# design.net
KiCad netlist of a schematic drawn in Altium Designer
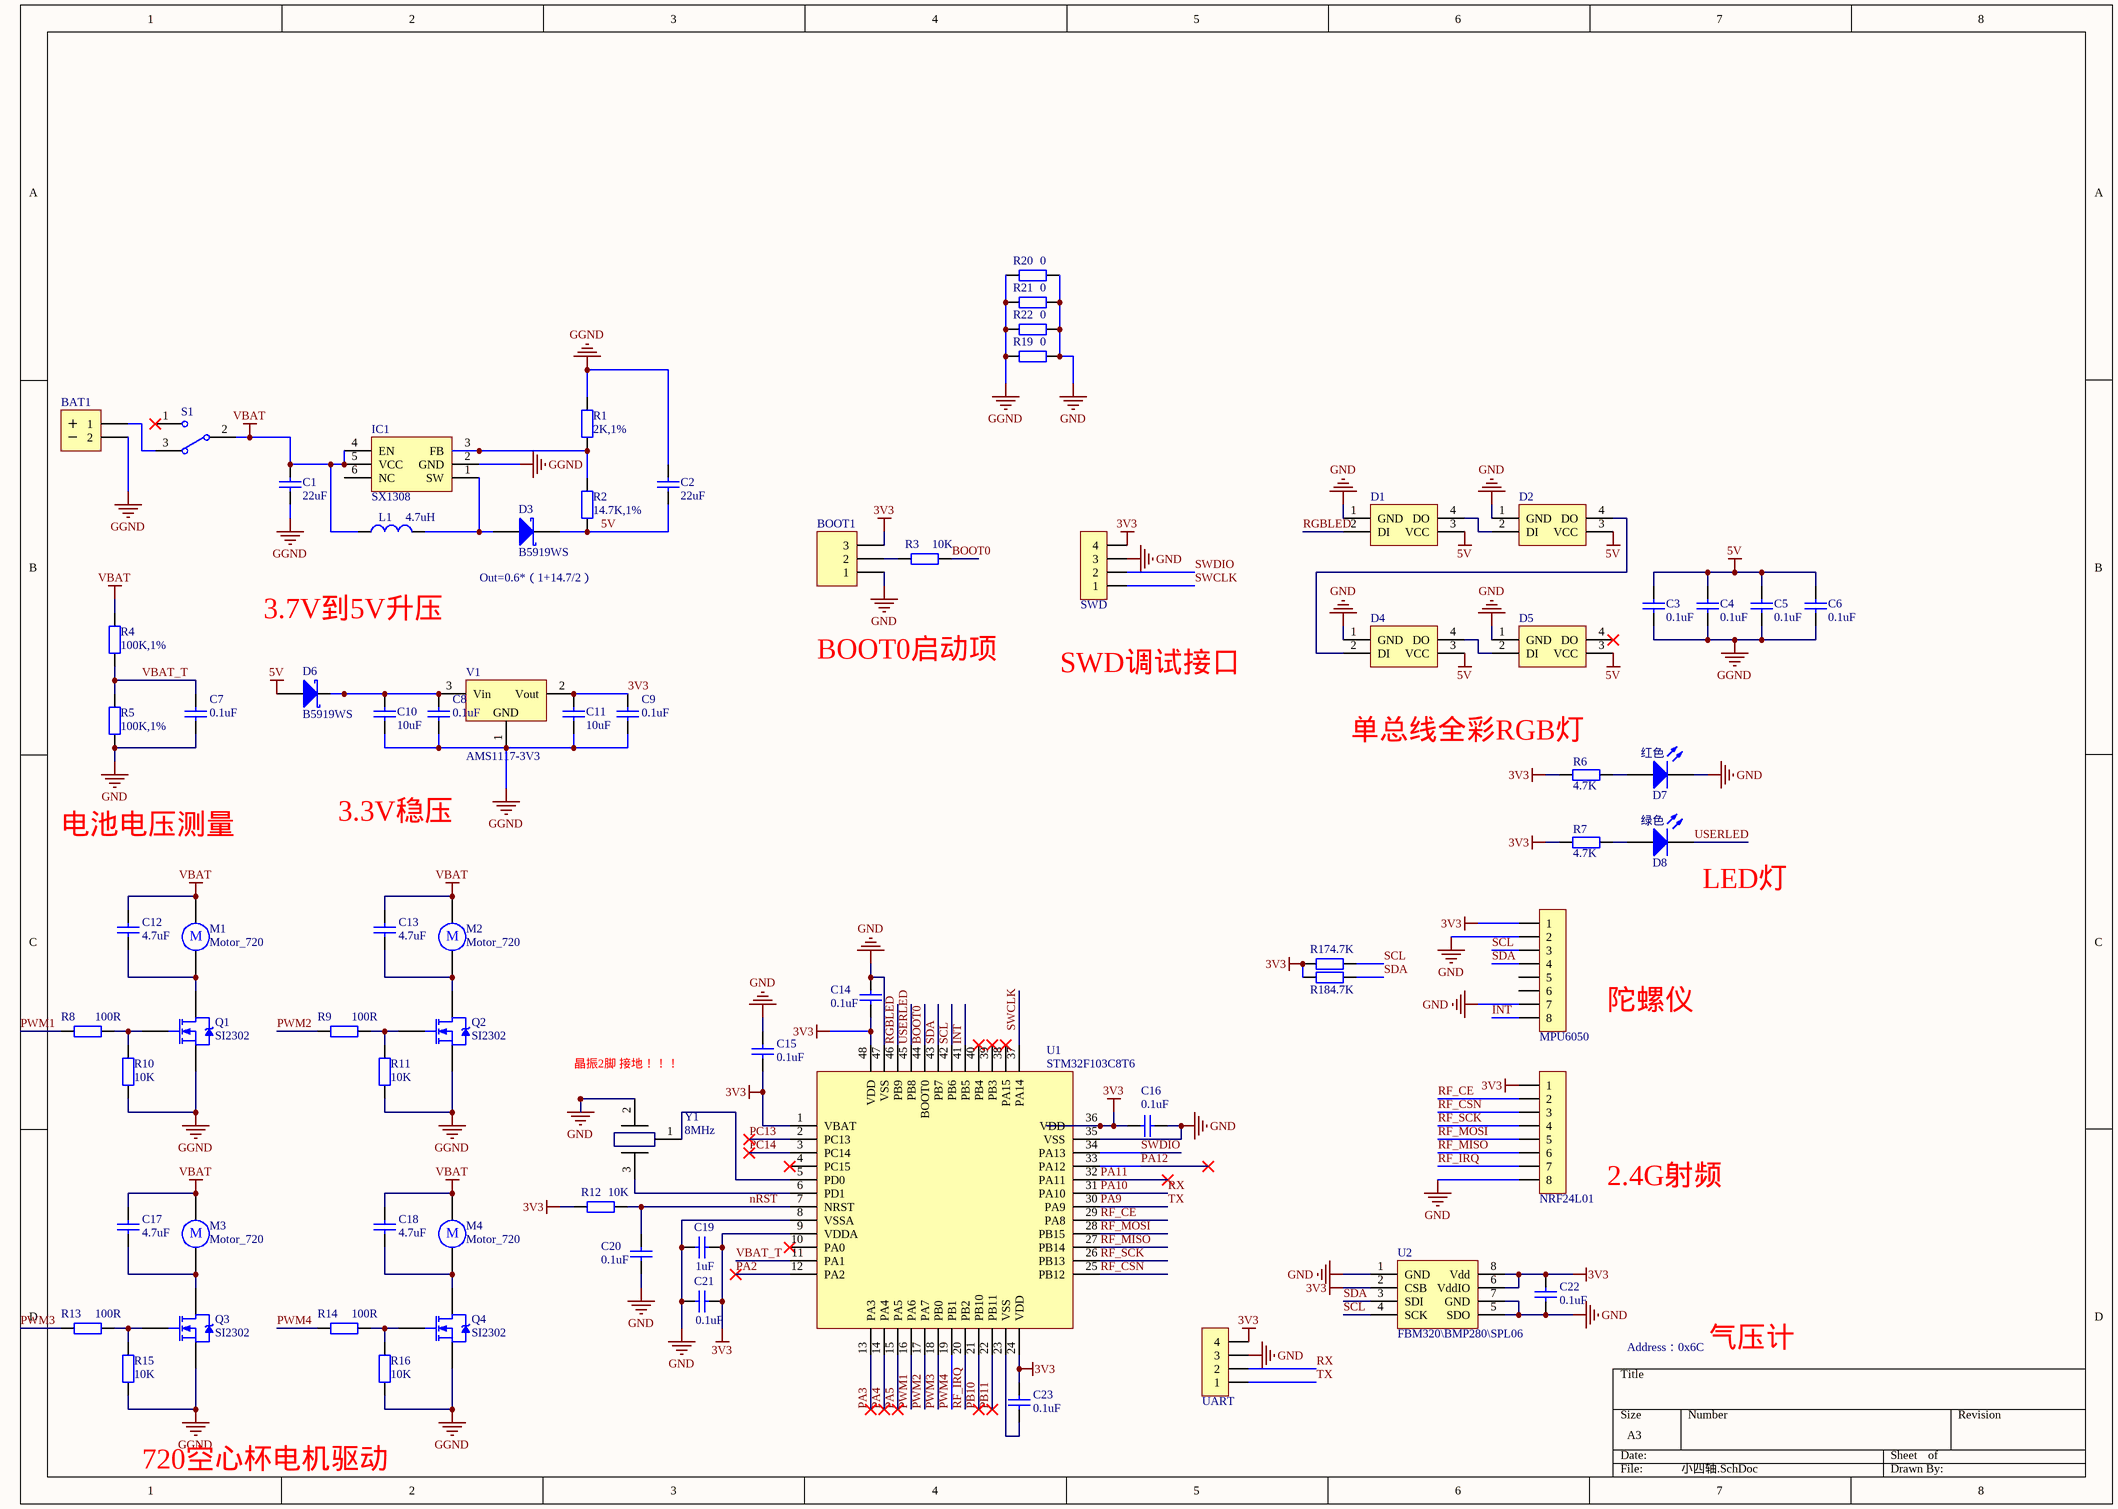
[diagram p0: 小四轴.SchDoc]

(export (version "E")
  (design (tool "Eeschema 10.0.6"))
  (components
    (comp (ref "BAT1")
      (value "BAT")
      (footprint "HDR2.54-LI-2P")
      (description "Header, 2-Pin")
      (fields (field (name "PUBLISHER") "mazhongwei"))
      (libsource (lib "RoboFly") (part "BAT"))
    )
    (comp (ref "BOOT1")
      (value "BOOT")
      (footprint "HDR2.54-LI-3P")
      (description "Header, 3-Pin")
      (fields (field (name "PUBLISHER") "Altium Limited"))
      (libsource (lib "RoboFly") (part "Header 3"))
    )
    (comp (ref "C1")
      (value "22uF")
      (footprint "C 0603_M")
      (fields (field (name "Comment") "C_0603") (field (name "PUBLISHER") "Altium Limited"))
      (libsource (lib "RoboFly") (part "C_0603"))
    )
    (comp (ref "C2")
      (value "22uF")
      (footprint "C 0603_M")
      (fields (field (name "Comment") "C_0603") (field (name "PUBLISHER") "Altium Limited"))
      (libsource (lib "RoboFly") (part "C_0603"))
    )
    (comp (ref "C3")
      (value "0.1uF")
      (footprint "C 0603_M")
      (fields (field (name "Comment") "C_0603") (field (name "PUBLISHER") "Altium Limited"))
      (libsource (lib "RoboFly") (part "C_0603"))
    )
    (comp (ref "C4")
      (value "0.1uF")
      (footprint "C 0603_M")
      (fields (field (name "Comment") "C_0603") (field (name "PUBLISHER") "Altium Limited"))
      (libsource (lib "RoboFly") (part "C_0603"))
    )
    (comp (ref "C5")
      (value "0.1uF")
      (footprint "C 0603_M")
      (fields (field (name "Comment") "C_0603") (field (name "PUBLISHER") "Altium Limited"))
      (libsource (lib "RoboFly") (part "C_0603"))
    )
    (comp (ref "C6")
      (value "0.1uF")
      (footprint "C 0603_M")
      (fields (field (name "Comment") "C_0603") (field (name "PUBLISHER") "Altium Limited"))
      (libsource (lib "RoboFly") (part "C_0603"))
    )
    (comp (ref "C7")
      (value "0.1uF")
      (footprint "C 0603_M")
      (fields (field (name "Comment") "C_0603") (field (name "PUBLISHER") "Altium Limited"))
      (libsource (lib "RoboFly") (part "C_0603"))
    )
    (comp (ref "C8")
      (value "0.1uF")
      (footprint "C 0603_M")
      (fields (field (name "Comment") "C_0603") (field (name "PUBLISHER") "Altium Limited"))
      (libsource (lib "RoboFly") (part "C_0603"))
    )
    (comp (ref "C9")
      (value "0.1uF")
      (footprint "C 0603_M")
      (fields (field (name "Comment") "C_0603") (field (name "PUBLISHER") "Altium Limited"))
      (libsource (lib "RoboFly") (part "C_0603"))
    )
    (comp (ref "C10")
      (value "10uF")
      (footprint "C 0603_M")
      (fields (field (name "Comment") "C_0603") (field (name "PUBLISHER") "Altium Limited"))
      (libsource (lib "RoboFly") (part "C_0603"))
    )
    (comp (ref "C11")
      (value "10uF")
      (footprint "C 0603_M")
      (fields (field (name "Comment") "C_0603") (field (name "PUBLISHER") "Altium Limited"))
      (libsource (lib "RoboFly") (part "C_0603"))
    )
    (comp (ref "C12")
      (value "4.7uF")
      (footprint "C 0603_M")
      (fields (field (name "Comment") "C_0603") (field (name "PUBLISHER") "Altium Limited"))
      (libsource (lib "RoboFly") (part "C_0603"))
    )
    (comp (ref "C13")
      (value "4.7uF")
      (footprint "C 0603_M")
      (fields (field (name "Comment") "C_0603") (field (name "PUBLISHER") "Altium Limited"))
      (libsource (lib "RoboFly") (part "C_0603"))
    )
    (comp (ref "C14")
      (value "0.1uF")
      (footprint "C 0603_M")
      (fields (field (name "Comment") "C_0603") (field (name "PUBLISHER") "Altium Limited"))
      (libsource (lib "RoboFly") (part "C_0603"))
    )
    (comp (ref "C15")
      (value "0.1uF")
      (footprint "C 0603_M")
      (fields (field (name "Comment") "C_0603") (field (name "PUBLISHER") "Altium Limited"))
      (libsource (lib "RoboFly") (part "C_0603"))
    )
    (comp (ref "C16")
      (value "0.1uF")
      (footprint "C 0603_M")
      (fields (field (name "Comment") "C_0603") (field (name "PUBLISHER") "Altium Limited"))
      (libsource (lib "RoboFly") (part "C_0603"))
    )
    (comp (ref "C17")
      (value "4.7uF")
      (footprint "C 0603_M")
      (fields (field (name "Comment") "C_0603") (field (name "PUBLISHER") "Altium Limited"))
      (libsource (lib "RoboFly") (part "C_0603"))
    )
    (comp (ref "C18")
      (value "4.7uF")
      (footprint "C 0603_M")
      (fields (field (name "Comment") "C_0603") (field (name "PUBLISHER") "Altium Limited"))
      (libsource (lib "RoboFly") (part "C_0603"))
    )
    (comp (ref "C19")
      (value "1uF")
      (footprint "C 0603_M")
      (fields (field (name "Comment") "C_0603") (field (name "PUBLISHER") "Altium Limited"))
      (libsource (lib "RoboFly") (part "C_0603"))
    )
    (comp (ref "C20")
      (value "0.1uF")
      (footprint "C 0603_M")
      (fields (field (name "Comment") "C_0603") (field (name "PUBLISHER") "Altium Limited"))
      (libsource (lib "RoboFly") (part "C_0603"))
    )
    (comp (ref "C21")
      (value "0.1uF")
      (footprint "C 0603_M")
      (fields (field (name "Comment") "C_0603") (field (name "PUBLISHER") "Altium Limited"))
      (libsource (lib "RoboFly") (part "C_0603"))
    )
    (comp (ref "C22")
      (value "0.1uF")
      (footprint "C 0603_M")
      (fields (field (name "Comment") "C_0603") (field (name "PUBLISHER") "Altium Limited"))
      (libsource (lib "RoboFly") (part "C_0603"))
    )
    (comp (ref "C23")
      (value "0.1uF")
      (footprint "C 0603_M")
      (fields (field (name "Comment") "C_0603") (field (name "PUBLISHER") "Altium Limited"))
      (libsource (lib "RoboFly") (part "C_0603"))
    )
    (comp (ref "D1")
      (value "P923D")
      (footprint "RGB_LED_5050")
      (fields (field (name "PUBLISHER") "mazhongwei"))
      (libsource (lib "RoboFly") (part "P923D"))
    )
    (comp (ref "D2")
      (value "P923D")
      (footprint "RGB_LED_5050")
      (fields (field (name "PUBLISHER") "mazhongwei"))
      (libsource (lib "RoboFly") (part "P923D"))
    )
    (comp (ref "D3")
      (value "B5919WS")
      (footprint "SOD-323")
      (description "肖特基二极管")
      (libsource (lib "二极管") (part "1N5819"))
    )
    (comp (ref "D4")
      (value "P923D")
      (footprint "RGB_LED_5050")
      (fields (field (name "PUBLISHER") "mazhongwei"))
      (libsource (lib "RoboFly") (part "P923D"))
    )
    (comp (ref "D5")
      (value "P923D")
      (footprint "RGB_LED_5050")
      (fields (field (name "PUBLISHER") "mazhongwei"))
      (libsource (lib "RoboFly") (part "P923D"))
    )
    (comp (ref "D6")
      (value "B5919WS")
      (footprint "SOD-323")
      (description "肖特基二极管")
      (libsource (lib "二极管") (part "1N5819"))
    )
    (comp (ref "D7")
      (value "红色")
      (footprint "LED 0603B")
      (description "发光二极管")
      (fields (field (name "PUBLISHER") "Altium Limited"))
      (libsource (lib "RoboFly") (part "LED 0603"))
    )
    (comp (ref "D8")
      (value "绿色")
      (footprint "LED 0603B")
      (description "发光二极管")
      (fields (field (name "PUBLISHER") "Altium Limited"))
      (libsource (lib "RoboFly") (part "LED 0603"))
    )
    (comp (ref "IC1")
      (value "SX1308")
      (footprint "SOT23-6N")
      (description "可调升压芯片")
      (fields (field (name "版权归属") "封装库来自淘宝 ID：黄晶宝石"))
      (libsource (lib "电源类芯片") (part "SX1308"))
    )
    (comp (ref "L1")
      (value "4.7uH")
      (footprint "SWPA4012S")
      (description "电感")
      (fields (field (name "Comment") "Inductor") (field (name "PUBLISHER") "Altium Limited"))
      (libsource (lib "RoboFly") (part "Inductor"))
    )
    (comp (ref "M1")
      (value "Motor_720")
      (footprint "ZH1.5-LI-2p")
      (description "Motor, General Kind")
      (fields (field (name "PUBLISHER") "mazhongwei"))
      (libsource (lib "RoboFly") (part "Motor_720"))
    )
    (comp (ref "M2")
      (value "Motor_720")
      (footprint "ZH1.5-LI-2p")
      (description "Motor, General Kind")
      (fields (field (name "PUBLISHER") "mazhongwei"))
      (libsource (lib "RoboFly") (part "Motor_720"))
    )
    (comp (ref "M3")
      (value "Motor_720")
      (footprint "ZH1.5-LI-2p")
      (description "Motor, General Kind")
      (fields (field (name "PUBLISHER") "mazhongwei"))
      (libsource (lib "RoboFly") (part "Motor_720"))
    )
    (comp (ref "M4")
      (value "Motor_720")
      (footprint "ZH1.5-LI-2p")
      (description "Motor, General Kind")
      (fields (field (name "PUBLISHER") "mazhongwei"))
      (libsource (lib "RoboFly") (part "Motor_720"))
    )
    (comp (ref "MPU6050")
      (value "HDR-1X8")
      (footprint "HDR2.54-LI-8P")
      (description "8P接插件")
      (fields (field (name "版权归属") "封装库来自淘宝 ID：黄晶宝石"))
      (libsource (lib "接插件-2.54MM") (part "Header 8"))
    )
    (comp (ref "NRF24L01")
      (value "HDR-1X8")
      (footprint "HDR1.27-LI-8P")
      (description "8P接插件")
      (libsource (lib "接插件-1.27MM") (part "Header 8"))
    )
    (comp (ref "Q1")
      (value "SI2302")
      (footprint "SOT23-3M")
      (description "N-Channel Power MOSFET")
      (fields (field (name "PUBLISHER") "mazhongwei"))
      (libsource (lib "RoboFly") (part "SI2302"))
    )
    (comp (ref "Q2")
      (value "SI2302")
      (footprint "SOT23-3M")
      (description "N-Channel Power MOSFET")
      (fields (field (name "PUBLISHER") "mazhongwei"))
      (libsource (lib "RoboFly") (part "SI2302"))
    )
    (comp (ref "Q3")
      (value "SI2302")
      (footprint "SOT23-3M")
      (description "N-Channel Power MOSFET")
      (fields (field (name "PUBLISHER") "mazhongwei"))
      (libsource (lib "RoboFly") (part "SI2302"))
    )
    (comp (ref "Q4")
      (value "SI2302")
      (footprint "SOT23-3M")
      (description "N-Channel Power MOSFET")
      (fields (field (name "PUBLISHER") "mazhongwei"))
      (libsource (lib "RoboFly") (part "SI2302"))
    )
    (comp (ref "R1")
      (value "2K,1%")
      (footprint "R 0603_M")
      (fields (field (name "Comment") "R_0603") (field (name "PUBLISHER") "Altium Limited"))
      (libsource (lib "") (part "R_0603_1"))
    )
    (comp (ref "R2")
      (value "14.7K,1%")
      (footprint "R 0603_M")
      (fields (field (name "Comment") "R_0603") (field (name "PUBLISHER") "Altium Limited"))
      (libsource (lib "") (part "R_0603_1"))
    )
    (comp (ref "R3")
      (value "10K")
      (footprint "R 0603_M")
      (fields (field (name "Comment") "R_0603") (field (name "PUBLISHER") "Altium Limited"))
      (libsource (lib "RoboFly") (part "R_0603"))
    )
    (comp (ref "R4")
      (value "100K,1%")
      (footprint "R 0603_M")
      (fields (field (name "Comment") "R_0603") (field (name "PUBLISHER") "Altium Limited"))
      (libsource (lib "") (part "R_0603_1"))
    )
    (comp (ref "R5")
      (value "100K,1%")
      (footprint "R 0603_M")
      (fields (field (name "Comment") "R_0603") (field (name "PUBLISHER") "Altium Limited"))
      (libsource (lib "") (part "R_0603_1"))
    )
    (comp (ref "R6")
      (value "4.7K")
      (footprint "R 0603_M")
      (fields (field (name "Comment") "R_0603") (field (name "PUBLISHER") "Altium Limited"))
      (libsource (lib "RoboFly") (part "R_0603"))
    )
    (comp (ref "R7")
      (value "4.7K")
      (footprint "R 0603_M")
      (fields (field (name "Comment") "R_0603") (field (name "PUBLISHER") "Altium Limited"))
      (libsource (lib "RoboFly") (part "R_0603"))
    )
    (comp (ref "R8")
      (value "100R")
      (footprint "R 0603_M")
      (fields (field (name "Comment") "R_0603") (field (name "PUBLISHER") "Altium Limited"))
      (libsource (lib "RoboFly") (part "R_0603"))
    )
    (comp (ref "R9")
      (value "100R")
      (footprint "R 0603_M")
      (fields (field (name "Comment") "R_0603") (field (name "PUBLISHER") "Altium Limited"))
      (libsource (lib "RoboFly") (part "R_0603"))
    )
    (comp (ref "R10")
      (value "10K")
      (footprint "R 0603_M")
      (fields (field (name "Comment") "R_0603") (field (name "PUBLISHER") "Altium Limited"))
      (libsource (lib "") (part "R_0603_1"))
    )
    (comp (ref "R11")
      (value "10K")
      (footprint "R 0603_M")
      (fields (field (name "Comment") "R_0603") (field (name "PUBLISHER") "Altium Limited"))
      (libsource (lib "") (part "R_0603_1"))
    )
    (comp (ref "R12")
      (value "10K")
      (footprint "R 0603_M")
      (fields (field (name "Comment") "R_0603") (field (name "PUBLISHER") "Altium Limited"))
      (libsource (lib "") (part "R_0603_2"))
    )
    (comp (ref "R13")
      (value "100R")
      (footprint "R 0603_M")
      (fields (field (name "Comment") "R_0603") (field (name "PUBLISHER") "Altium Limited"))
      (libsource (lib "RoboFly") (part "R_0603"))
    )
    (comp (ref "R14")
      (value "100R")
      (footprint "R 0603_M")
      (fields (field (name "Comment") "R_0603") (field (name "PUBLISHER") "Altium Limited"))
      (libsource (lib "RoboFly") (part "R_0603"))
    )
    (comp (ref "R15")
      (value "10K")
      (footprint "R 0603_M")
      (fields (field (name "Comment") "R_0603") (field (name "PUBLISHER") "Altium Limited"))
      (libsource (lib "") (part "R_0603_1"))
    )
    (comp (ref "R16")
      (value "10K")
      (footprint "R 0603_M")
      (fields (field (name "Comment") "R_0603") (field (name "PUBLISHER") "Altium Limited"))
      (libsource (lib "") (part "R_0603_1"))
    )
    (comp (ref "R17")
      (value "4.7K")
      (footprint "R 0603_M")
      (fields (field (name "Comment") "R_0603") (field (name "PUBLISHER") "Altium Limited"))
      (libsource (lib "RoboFly") (part "R_0603"))
    )
    (comp (ref "R18")
      (value "4.7K")
      (footprint "R 0603_M")
      (fields (field (name "Comment") "R_0603") (field (name "PUBLISHER") "Altium Limited"))
      (libsource (lib "RoboFly") (part "R_0603"))
    )
    (comp (ref "R19")
      (value "0")
      (footprint "R 0603_M")
      (fields (field (name "Comment") "R_0603") (field (name "PUBLISHER") "Altium Limited"))
      (libsource (lib "RoboFly") (part "R_0603"))
    )
    (comp (ref "R20")
      (value "0")
      (footprint "R 0603_M")
      (fields (field (name "Comment") "R_0603") (field (name "PUBLISHER") "Altium Limited"))
      (libsource (lib "RoboFly") (part "R_0603"))
    )
    (comp (ref "R21")
      (value "0")
      (footprint "R 0603_M")
      (fields (field (name "Comment") "R_0603") (field (name "PUBLISHER") "Altium Limited"))
      (libsource (lib "RoboFly") (part "R_0603"))
    )
    (comp (ref "R22")
      (value "0")
      (footprint "R 0603_M")
      (fields (field (name "Comment") "R_0603") (field (name "PUBLISHER") "Altium Limited"))
      (libsource (lib "RoboFly") (part "R_0603"))
    )
    (comp (ref "S1")
      (value "SW-SPDT")
      (footprint "SW-TH_OS102011MS2QN1")
      (description "SPDT Subminiature Toggle Switch, Right Angle Mounting, Vertical Actuation")
      (fields (field (name "PUBLISHER") "mazhongwei"))
      (libsource (lib "RoboFly") (part "SW-SPDT"))
    )
    (comp (ref "SWD")
      (value "HDR-1X4")
      (footprint "HDR2.54-LI-4P")
      (description "4P接插件")
      (fields (field (name "版权归属") "封装库来自淘宝 ID：黄晶宝石"))
      (libsource (lib "接插件-2.54MM") (part "Header 4"))
    )
    (comp (ref "U1")
      (value "STM32F103C8T6")
      (footprint "LQFP48-7*7")
      (libsource (lib "RoboFly") (part "STM32F103C8T6"))
    )
    (comp (ref "U2")
      (value "FBM32~{0}BMP28~{0}SPL06")
      (footprint "SENSOR-TH_BMP280-BL")
      (description "气压计")
      (fields (field (name "PUBLISHER") "mazhongwei"))
      (libsource (lib "RoboFly") (part "FBM320"))
    )
    (comp (ref "UART")
      (value "HDR-1X4")
      (footprint "HDR2.54-LI-4P")
      (description "4P接插件")
      (fields (field (name "版权归属") "封装库来自淘宝 ID：黄晶宝石"))
      (libsource (lib "接插件-2.54MM") (part "Header 4"))
    )
    (comp (ref "V1")
      (value "AMS1117-3V3")
      (footprint "SOT223_L")
      (description "三端稳压芯片")
      (libsource (lib "电源类芯片") (part "AMS1117"))
    )
    (comp (ref "Y1")
      (value "8MHz")
      (footprint "OSC-SMD_3P-L3.2-W1.3-P1.20-L")
      (fields (field (name "Comment") "XTAL") (field (name "PUBLISHER") "mazhongwei"))
      (libsource (lib "RoboFly") (part "XTAL_2"))
    )
  )
  (nets
    (net (code "1") (name "/BOOT0") (class "Default")
      (node (ref "R3") (pin "2") (pinfunction "2_2") (pintype "passive"))
      (node (ref "U1") (pin "44") (pinfunction "BOOT0_44") (pintype "passive"))
    )
    (net (code "2") (name "/INT") (class "Default")
      (node (ref "MPU6050") (pin "8") (pinfunction "8_8") (pintype "passive"))
      (node (ref "U1") (pin "41") (pinfunction "PB5_41") (pintype "passive"))
    )
    (net (code "3") (name "/PA2") (class "Default")
      (node (ref "U1") (pin "12") (pinfunction "PA2_12") (pintype "passive+no_connect"))
    )
    (net (code "4") (name "/PA3") (class "Default")
      (node (ref "U1") (pin "13") (pinfunction "PA3_13") (pintype "passive+no_connect"))
    )
    (net (code "5") (name "/PA4") (class "Default")
      (node (ref "U1") (pin "14") (pinfunction "PA4_14") (pintype "passive+no_connect"))
    )
    (net (code "6") (name "/PA5") (class "Default")
      (node (ref "U1") (pin "15") (pinfunction "PA5_15") (pintype "passive+no_connect"))
    )
    (net (code "7") (name "/PA9") (class "Default")
      (node (ref "U1") (pin "30") (pinfunction "PA9_30") (pintype "passive"))
      (node (ref "UART") (pin "1") (pinfunction "1_1") (pintype "passive"))
    )
    (net (code "8") (name "/PA10") (class "Default")
      (node (ref "U1") (pin "31") (pinfunction "PA10_31") (pintype "passive"))
      (node (ref "UART") (pin "2") (pinfunction "2_2") (pintype "passive"))
    )
    (net (code "9") (name "/PA11") (class "Default")
      (node (ref "U1") (pin "32") (pinfunction "PA11_32") (pintype "passive+no_connect"))
    )
    (net (code "10") (name "/PA12") (class "Default")
      (node (ref "U1") (pin "33") (pinfunction "PA12_33") (pintype "passive+no_connect"))
    )
    (net (code "11") (name "/PB10") (class "Default")
      (node (ref "U1") (pin "21") (pinfunction "PB10_21") (pintype "passive+no_connect"))
    )
    (net (code "12") (name "/PB11") (class "Default")
      (node (ref "U1") (pin "22") (pinfunction "PB11_22") (pintype "passive+no_connect"))
    )
    (net (code "13") (name "/PC13") (class "Default")
      (node (ref "U1") (pin "2") (pinfunction "PC13_2") (pintype "passive+no_connect"))
    )
    (net (code "14") (name "/PC14") (class "Default")
      (node (ref "U1") (pin "3") (pinfunction "PC14_3") (pintype "passive+no_connect"))
    )
    (net (code "15") (name "/PWM1") (class "Default")
      (node (ref "R8") (pin "1") (pinfunction "1_1") (pintype "passive"))
      (node (ref "U1") (pin "16") (pinfunction "PA6_16") (pintype "passive"))
    )
    (net (code "16") (name "/PWM2") (class "Default")
      (node (ref "R9") (pin "1") (pinfunction "1_1") (pintype "passive"))
      (node (ref "U1") (pin "17") (pinfunction "PA7_17") (pintype "passive"))
    )
    (net (code "17") (name "/PWM3") (class "Default")
      (node (ref "R13") (pin "1") (pinfunction "1_1") (pintype "passive"))
      (node (ref "U1") (pin "18") (pinfunction "PB0_18") (pintype "passive"))
    )
    (net (code "18") (name "/PWM4") (class "Default")
      (node (ref "R14") (pin "1") (pinfunction "1_1") (pintype "passive"))
      (node (ref "U1") (pin "19") (pinfunction "PB1_19") (pintype "passive"))
    )
    (net (code "19") (name "/RF_CE") (class "Default")
      (node (ref "NRF24L01") (pin "2") (pinfunction "2_2") (pintype "passive"))
      (node (ref "U1") (pin "29") (pinfunction "PA8_29") (pintype "passive"))
    )
    (net (code "20") (name "/RF_CSN") (class "Default")
      (node (ref "NRF24L01") (pin "3") (pinfunction "3_3") (pintype "passive"))
      (node (ref "U1") (pin "25") (pinfunction "PB12_25") (pintype "passive"))
    )
    (net (code "21") (name "/RF_IRQ") (class "Default")
      (node (ref "NRF24L01") (pin "7") (pinfunction "7_7") (pintype "passive"))
      (node (ref "U1") (pin "20") (pinfunction "PB2_20") (pintype "passive"))
    )
    (net (code "22") (name "/RF_MISO") (class "Default")
      (node (ref "NRF24L01") (pin "6") (pinfunction "6_6") (pintype "passive"))
      (node (ref "U1") (pin "27") (pinfunction "PB14_27") (pintype "passive"))
    )
    (net (code "23") (name "/RF_MOSI") (class "Default")
      (node (ref "NRF24L01") (pin "5") (pinfunction "5_5") (pintype "passive"))
      (node (ref "U1") (pin "28") (pinfunction "PB15_28") (pintype "passive"))
    )
    (net (code "24") (name "/RF_SCK") (class "Default")
      (node (ref "NRF24L01") (pin "4") (pinfunction "4_4") (pintype "passive"))
      (node (ref "U1") (pin "26") (pinfunction "PB13_26") (pintype "passive"))
    )
    (net (code "25") (name "/RGBLED") (class "Default")
      (node (ref "D1") (pin "2") (pinfunction "DI_2") (pintype "passive"))
      (node (ref "U1") (pin "46") (pinfunction "PB9_46") (pintype "passive"))
    )
    (net (code "26") (name "/SCL") (class "Default")
      (node (ref "MPU6050") (pin "3") (pinfunction "3_3") (pintype "passive"))
      (node (ref "R17") (pin "2") (pinfunction "2_2") (pintype "passive"))
      (node (ref "U1") (pin "42") (pinfunction "PB6_42") (pintype "passive"))
      (node (ref "U2") (pin "4") (pinfunction "SCK_4") (pintype "passive"))
    )
    (net (code "27") (name "/SDA") (class "Default")
      (node (ref "MPU6050") (pin "4") (pinfunction "4_4") (pintype "passive"))
      (node (ref "R18") (pin "2") (pinfunction "2_2") (pintype "passive"))
      (node (ref "U1") (pin "43") (pinfunction "PB7_43") (pintype "passive"))
      (node (ref "U2") (pin "3") (pinfunction "SDI_3") (pintype "passive"))
    )
    (net (code "28") (name "/SWCLK") (class "Default")
      (node (ref "SWD") (pin "1") (pinfunction "1_1") (pintype "passive"))
      (node (ref "U1") (pin "37") (pinfunction "PA14_37") (pintype "passive"))
    )
    (net (code "29") (name "/SWDIO") (class "Default")
      (node (ref "SWD") (pin "2") (pinfunction "2_2") (pintype "passive"))
      (node (ref "U1") (pin "34") (pinfunction "PA13_34") (pintype "passive"))
    )
    (net (code "30") (name "/USERLED") (class "Default")
      (node (ref "D8") (pin "2") (pinfunction "2_2") (pintype "passive"))
      (node (ref "U1") (pin "45") (pinfunction "PB8_45") (pintype "passive"))
    )
    (net (code "31") (name "/VBAT_T") (class "Default")
      (node (ref "C7") (pin "2") (pinfunction "2_2") (pintype "passive"))
      (node (ref "R4") (pin "1") (pinfunction "1_1") (pintype "passive"))
      (node (ref "R5") (pin "2") (pinfunction "2_2") (pintype "passive"))
      (node (ref "U1") (pin "11") (pinfunction "PA1_11") (pintype "passive"))
    )
    (net (code "32") (name "/nRST") (class "Default")
      (node (ref "C20") (pin "2") (pinfunction "2_2") (pintype "passive"))
      (node (ref "R12") (pin "1") (pinfunction "1_1") (pintype "passive"))
      (node (ref "U1") (pin "7") (pinfunction "NRST_7") (pintype "passive"))
    )
    (net (code "33") (name "3V3") (class "Default")
      (node (ref "BOOT1") (pin "3") (pinfunction "3_3") (pintype "passive"))
      (node (ref "C11") (pin "2") (pinfunction "2_2") (pintype "passive"))
      (node (ref "C14") (pin "1") (pinfunction "1_1") (pintype "passive"))
      (node (ref "C15") (pin "2") (pinfunction "2_2") (pintype "passive"))
      (node (ref "C16") (pin "2") (pinfunction "2_2") (pintype "passive"))
      (node (ref "C19") (pin "2") (pinfunction "2_2") (pintype "passive"))
      (node (ref "C21") (pin "2") (pinfunction "2_2") (pintype "passive"))
      (node (ref "C22") (pin "1") (pinfunction "1_1") (pintype "passive"))
      (node (ref "C23") (pin "1") (pinfunction "1_1") (pintype "passive"))
      (node (ref "C9") (pin "2") (pinfunction "2_2") (pintype "passive"))
      (node (ref "MPU6050") (pin "1") (pinfunction "1_1") (pintype "passive"))
      (node (ref "NRF24L01") (pin "1") (pinfunction "1_1") (pintype "passive"))
      (node (ref "R12") (pin "2") (pinfunction "2_2") (pintype "passive"))
      (node (ref "R17") (pin "1") (pinfunction "1_1") (pintype "passive"))
      (node (ref "R18") (pin "1") (pinfunction "1_1") (pintype "passive"))
      (node (ref "R6") (pin "1") (pinfunction "1_1") (pintype "passive"))
      (node (ref "R7") (pin "1") (pinfunction "1_1") (pintype "passive"))
      (node (ref "SWD") (pin "4") (pinfunction "4_4") (pintype "passive"))
      (node (ref "U1") (pin "1") (pinfunction "VBAT_1") (pintype "passive"))
      (node (ref "U1") (pin "24") (pinfunction "VDD_24") (pintype "passive"))
      (node (ref "U1") (pin "36") (pinfunction "VDD_36") (pintype "passive"))
      (node (ref "U1") (pin "48") (pinfunction "VDD_48") (pintype "passive"))
      (node (ref "U1") (pin "9") (pinfunction "VDDA_9") (pintype "passive"))
      (node (ref "U2") (pin "2") (pinfunction "CSB_2") (pintype "passive"))
      (node (ref "U2") (pin "6") (pinfunction "VddIO_6") (pintype "passive"))
      (node (ref "U2") (pin "8") (pinfunction "Vdd_8") (pintype "passive"))
      (node (ref "UART") (pin "4") (pinfunction "4_4") (pintype "passive"))
      (node (ref "V1") (pin "2") (pinfunction "Vout_2") (pintype "passive"))
    )
    (net (code "34") (name "5V") (class "Default")
      (node (ref "C2") (pin "1") (pinfunction "1_1") (pintype "passive"))
      (node (ref "C3") (pin "2") (pinfunction "2_2") (pintype "passive"))
      (node (ref "C4") (pin "2") (pinfunction "2_2") (pintype "passive"))
      (node (ref "C5") (pin "2") (pinfunction "2_2") (pintype "passive"))
      (node (ref "C6") (pin "2") (pinfunction "2_2") (pintype "passive"))
      (node (ref "D1") (pin "3") (pinfunction "VCC_3") (pintype "passive"))
      (node (ref "D2") (pin "3") (pinfunction "VCC_3") (pintype "passive"))
      (node (ref "D3") (pin "2") (pinfunction "K_2") (pintype "passive"))
      (node (ref "D4") (pin "3") (pinfunction "VCC_3") (pintype "passive"))
      (node (ref "D5") (pin "3") (pinfunction "VCC_3") (pintype "passive"))
      (node (ref "D6") (pin "1") (pinfunction "A_1") (pintype "passive"))
      (node (ref "R2") (pin "1") (pinfunction "1_1") (pintype "passive"))
    )
    (net (code "35") (name "GGND") (class "Default")
      (node (ref "BAT1") (pin "2") (pinfunction "2_2") (pintype "passive"))
      (node (ref "C1") (pin "1") (pinfunction "1_1") (pintype "passive"))
      (node (ref "C10") (pin "1") (pinfunction "1_1") (pintype "passive"))
      (node (ref "C11") (pin "1") (pinfunction "1_1") (pintype "passive"))
      (node (ref "C2") (pin "2") (pinfunction "2_2") (pintype "passive"))
      (node (ref "C3") (pin "1") (pinfunction "1_1") (pintype "passive"))
      (node (ref "C4") (pin "1") (pinfunction "1_1") (pintype "passive"))
      (node (ref "C5") (pin "1") (pinfunction "1_1") (pintype "passive"))
      (node (ref "C6") (pin "1") (pinfunction "1_1") (pintype "passive"))
      (node (ref "C8") (pin "1") (pinfunction "1_1") (pintype "passive"))
      (node (ref "C9") (pin "1") (pinfunction "1_1") (pintype "passive"))
      (node (ref "IC1") (pin "2") (pinfunction "GND_2") (pintype "passive"))
      (node (ref "Q1") (pin "2") (pinfunction "S_2") (pintype "passive"))
      (node (ref "Q2") (pin "2") (pinfunction "S_2") (pintype "passive"))
      (node (ref "Q3") (pin "2") (pinfunction "S_2") (pintype "passive"))
      (node (ref "Q4") (pin "2") (pinfunction "S_2") (pintype "passive"))
      (node (ref "R1") (pin "2") (pinfunction "2_2") (pintype "passive"))
      (node (ref "R10") (pin "1") (pinfunction "1_1") (pintype "passive"))
      (node (ref "R11") (pin "1") (pinfunction "1_1") (pintype "passive"))
      (node (ref "R15") (pin "1") (pinfunction "1_1") (pintype "passive"))
      (node (ref "R16") (pin "1") (pinfunction "1_1") (pintype "passive"))
      (node (ref "R19") (pin "1") (pinfunction "1_1") (pintype "passive"))
      (node (ref "R20") (pin "1") (pinfunction "1_1") (pintype "passive"))
      (node (ref "R21") (pin "1") (pinfunction "1_1") (pintype "passive"))
      (node (ref "R22") (pin "1") (pinfunction "1_1") (pintype "passive"))
      (node (ref "V1") (pin "1") (pinfunction "GND_1") (pintype "passive"))
    )
    (net (code "36") (name "GND") (class "Default")
      (node (ref "BOOT1") (pin "1") (pinfunction "1_1") (pintype "passive"))
      (node (ref "C14") (pin "2") (pinfunction "2_2") (pintype "passive"))
      (node (ref "C15") (pin "1") (pinfunction "1_1") (pintype "passive"))
      (node (ref "C16") (pin "1") (pinfunction "1_1") (pintype "passive"))
      (node (ref "C19") (pin "1") (pinfunction "1_1") (pintype "passive"))
      (node (ref "C20") (pin "1") (pinfunction "1_1") (pintype "passive"))
      (node (ref "C21") (pin "1") (pinfunction "1_1") (pintype "passive"))
      (node (ref "C22") (pin "2") (pinfunction "2_2") (pintype "passive"))
      (node (ref "C7") (pin "1") (pinfunction "1_1") (pintype "passive"))
      (node (ref "D1") (pin "1") (pinfunction "GND_1") (pintype "passive"))
      (node (ref "D2") (pin "1") (pinfunction "GND_1") (pintype "passive"))
      (node (ref "D4") (pin "1") (pinfunction "GND_1") (pintype "passive"))
      (node (ref "D5") (pin "1") (pinfunction "GND_1") (pintype "passive"))
      (node (ref "D7") (pin "2") (pinfunction "2_2") (pintype "passive"))
      (node (ref "MPU6050") (pin "2") (pinfunction "2_2") (pintype "passive"))
      (node (ref "MPU6050") (pin "7") (pinfunction "7_7") (pintype "passive"))
      (node (ref "NRF24L01") (pin "8") (pinfunction "8_8") (pintype "passive"))
      (node (ref "R19") (pin "2") (pinfunction "2_2") (pintype "passive"))
      (node (ref "R20") (pin "2") (pinfunction "2_2") (pintype "passive"))
      (node (ref "R21") (pin "2") (pinfunction "2_2") (pintype "passive"))
      (node (ref "R22") (pin "2") (pinfunction "2_2") (pintype "passive"))
      (node (ref "R5") (pin "1") (pinfunction "1_1") (pintype "passive"))
      (node (ref "SWD") (pin "3") (pinfunction "3_3") (pintype "passive"))
      (node (ref "U1") (pin "35") (pinfunction "VSS_35") (pintype "passive"))
      (node (ref "U1") (pin "47") (pinfunction "VSS_47") (pintype "passive"))
      (node (ref "U1") (pin "8") (pinfunction "VSSA_8") (pintype "passive"))
      (node (ref "U2") (pin "1") (pinfunction "GND_1") (pintype "passive"))
      (node (ref "U2") (pin "5") (pinfunction "SDO_5") (pintype "passive"))
      (node (ref "U2") (pin "7") (pinfunction "GND_7") (pintype "passive"))
      (node (ref "UART") (pin "3") (pinfunction "3_3") (pintype "passive"))
      (node (ref "Y1") (pin "2") (pinfunction "2_2") (pintype "passive"))
    )
    (net (code "37") (name "Net-(BAT1-Pad1)") (class "Default")
      (node (ref "BAT1") (pin "1") (pinfunction "1_1") (pintype "passive"))
      (node (ref "S1") (pin "3") (pinfunction "3_3") (pintype "passive"))
    )
    (net (code "38") (name "Net-(BOOT1-Pad2)") (class "Default")
      (node (ref "BOOT1") (pin "2") (pinfunction "2_2") (pintype "passive"))
      (node (ref "R3") (pin "1") (pinfunction "1_1") (pintype "passive"))
    )
    (net (code "39") (name "Net-(C23-Pad2)") (class "Default")
      (node (ref "C23") (pin "2") (pinfunction "2_2") (pintype "passive"))
      (node (ref "U1") (pin "23") (pinfunction "VSS_23") (pintype "passive"))
    )
    (net (code "40") (name "Net-(D1-DO)") (class "Default")
      (node (ref "D1") (pin "4") (pinfunction "DO_4") (pintype "passive"))
      (node (ref "D2") (pin "2") (pinfunction "DI_2") (pintype "passive"))
    )
    (net (code "41") (name "Net-(D2-DO)") (class "Default")
      (node (ref "D2") (pin "4") (pinfunction "DO_4") (pintype "passive"))
      (node (ref "D4") (pin "2") (pinfunction "DI_2") (pintype "passive"))
    )
    (net (code "42") (name "Net-(D3-A)") (class "Default")
      (node (ref "D3") (pin "1") (pinfunction "A_1") (pintype "passive"))
      (node (ref "IC1") (pin "1") (pinfunction "SW_1") (pintype "passive"))
      (node (ref "L1") (pin "2") (pinfunction "2_2") (pintype "passive"))
    )
    (net (code "43") (name "Net-(D4-DO)") (class "Default")
      (node (ref "D4") (pin "4") (pinfunction "DO_4") (pintype "passive"))
      (node (ref "D5") (pin "2") (pinfunction "DI_2") (pintype "passive"))
    )
    (net (code "44") (name "Net-(D6-K)") (class "Default")
      (node (ref "C10") (pin "2") (pinfunction "2_2") (pintype "passive"))
      (node (ref "C8") (pin "2") (pinfunction "2_2") (pintype "passive"))
      (node (ref "D6") (pin "2") (pinfunction "K_2") (pintype "passive"))
      (node (ref "V1") (pin "3") (pinfunction "Vin_3") (pintype "passive"))
    )
    (net (code "45") (name "Net-(D7-Pad1)") (class "Default")
      (node (ref "D7") (pin "1") (pinfunction "1_1") (pintype "passive"))
      (node (ref "R6") (pin "2") (pinfunction "2_2") (pintype "passive"))
    )
    (net (code "46") (name "Net-(D8-Pad1)") (class "Default")
      (node (ref "D8") (pin "1") (pinfunction "1_1") (pintype "passive"))
      (node (ref "R7") (pin "2") (pinfunction "2_2") (pintype "passive"))
    )
    (net (code "47") (name "Net-(IC1-FB)") (class "Default")
      (node (ref "IC1") (pin "3") (pinfunction "FB_3") (pintype "passive"))
      (node (ref "R1") (pin "1") (pinfunction "1_1") (pintype "passive"))
      (node (ref "R2") (pin "2") (pinfunction "2_2") (pintype "passive"))
    )
    (net (code "48") (name "Net-(Q1-D)") (class "Default")
      (node (ref "C12") (pin "1") (pinfunction "1_1") (pintype "passive"))
      (node (ref "M1") (pin "2") (pinfunction "2_2") (pintype "passive"))
      (node (ref "Q1") (pin "3") (pinfunction "D_3") (pintype "passive"))
    )
    (net (code "49") (name "Net-(Q1-G)") (class "Default")
      (node (ref "Q1") (pin "1") (pinfunction "G_1") (pintype "passive"))
      (node (ref "R10") (pin "2") (pinfunction "2_2") (pintype "passive"))
      (node (ref "R8") (pin "2") (pinfunction "2_2") (pintype "passive"))
    )
    (net (code "50") (name "Net-(Q2-D)") (class "Default")
      (node (ref "C13") (pin "1") (pinfunction "1_1") (pintype "passive"))
      (node (ref "M2") (pin "2") (pinfunction "2_2") (pintype "passive"))
      (node (ref "Q2") (pin "3") (pinfunction "D_3") (pintype "passive"))
    )
    (net (code "51") (name "Net-(Q2-G)") (class "Default")
      (node (ref "Q2") (pin "1") (pinfunction "G_1") (pintype "passive"))
      (node (ref "R11") (pin "2") (pinfunction "2_2") (pintype "passive"))
      (node (ref "R9") (pin "2") (pinfunction "2_2") (pintype "passive"))
    )
    (net (code "52") (name "Net-(Q3-D)") (class "Default")
      (node (ref "C17") (pin "1") (pinfunction "1_1") (pintype "passive"))
      (node (ref "M3") (pin "2") (pinfunction "2_2") (pintype "passive"))
      (node (ref "Q3") (pin "3") (pinfunction "D_3") (pintype "passive"))
    )
    (net (code "53") (name "Net-(Q3-G)") (class "Default")
      (node (ref "Q3") (pin "1") (pinfunction "G_1") (pintype "passive"))
      (node (ref "R13") (pin "2") (pinfunction "2_2") (pintype "passive"))
      (node (ref "R15") (pin "2") (pinfunction "2_2") (pintype "passive"))
    )
    (net (code "54") (name "Net-(Q4-D)") (class "Default")
      (node (ref "C18") (pin "1") (pinfunction "1_1") (pintype "passive"))
      (node (ref "M4") (pin "2") (pinfunction "2_2") (pintype "passive"))
      (node (ref "Q4") (pin "3") (pinfunction "D_3") (pintype "passive"))
    )
    (net (code "55") (name "Net-(Q4-G)") (class "Default")
      (node (ref "Q4") (pin "1") (pinfunction "G_1") (pintype "passive"))
      (node (ref "R14") (pin "2") (pinfunction "2_2") (pintype "passive"))
      (node (ref "R16") (pin "2") (pinfunction "2_2") (pintype "passive"))
    )
    (net (code "56") (name "Net-(U1-PD0)") (class "Default")
      (node (ref "U1") (pin "5") (pinfunction "PD0_5") (pintype "passive"))
      (node (ref "Y1") (pin "1") (pinfunction "1_1") (pintype "passive"))
    )
    (net (code "57") (name "Net-(U1-PD1)") (class "Default")
      (node (ref "U1") (pin "6") (pinfunction "PD1_6") (pintype "passive"))
      (node (ref "Y1") (pin "3") (pinfunction "3_3") (pintype "passive"))
    )
    (net (code "58") (name "VBAT") (class "Default")
      (node (ref "C1") (pin "2") (pinfunction "2_2") (pintype "passive"))
      (node (ref "C12") (pin "2") (pinfunction "2_2") (pintype "passive"))
      (node (ref "C13") (pin "2") (pinfunction "2_2") (pintype "passive"))
      (node (ref "C17") (pin "2") (pinfunction "2_2") (pintype "passive"))
      (node (ref "C18") (pin "2") (pinfunction "2_2") (pintype "passive"))
      (node (ref "IC1") (pin "4") (pinfunction "EN_4") (pintype "passive"))
      (node (ref "IC1") (pin "5") (pinfunction "VCC_5") (pintype "passive"))
      (node (ref "L1") (pin "1") (pinfunction "1_1") (pintype "passive"))
      (node (ref "M1") (pin "1") (pinfunction "1_1") (pintype "passive"))
      (node (ref "M2") (pin "1") (pinfunction "1_1") (pintype "passive"))
      (node (ref "M3") (pin "1") (pinfunction "1_1") (pintype "passive"))
      (node (ref "M4") (pin "1") (pinfunction "1_1") (pintype "passive"))
      (node (ref "R4") (pin "2") (pinfunction "2_2") (pintype "passive"))
      (node (ref "S1") (pin "2") (pinfunction "2_2") (pintype "passive"))
    )
    (net (code "59") (name "unconnected-(D5-DO-Pad4)") (class "Default")
      (node (ref "D5") (pin "4") (pinfunction "DO_4") (pintype "passive+no_connect"))
    )
    (net (code "60") (name "unconnected-(IC1-NC-Pad6)") (class "Default")
      (node (ref "IC1") (pin "6") (pinfunction "NC_6") (pintype "passive"))
    )
    (net (code "61") (name "unconnected-(MPU6050-Pad5)") (class "Default")
      (node (ref "MPU6050") (pin "5") (pinfunction "5_5") (pintype "passive"))
    )
    (net (code "62") (name "unconnected-(MPU6050-Pad6)") (class "Default")
      (node (ref "MPU6050") (pin "6") (pinfunction "6_6") (pintype "passive"))
    )
    (net (code "63") (name "unconnected-(S1-Pad1)") (class "Default")
      (node (ref "S1") (pin "1") (pinfunction "1_1") (pintype "passive+no_connect"))
    )
    (net (code "64") (name "unconnected-(U1-PA0-Pad10)") (class "Default")
      (node (ref "U1") (pin "10") (pinfunction "PA0_10") (pintype "passive+no_connect"))
    )
    (net (code "65") (name "unconnected-(U1-PA15-Pad38)") (class "Default")
      (node (ref "U1") (pin "38") (pinfunction "PA15_38") (pintype "passive+no_connect"))
    )
    (net (code "66") (name "unconnected-(U1-PB3-Pad39)") (class "Default")
      (node (ref "U1") (pin "39") (pinfunction "PB3_39") (pintype "passive+no_connect"))
    )
    (net (code "67") (name "unconnected-(U1-PB4-Pad40)") (class "Default")
      (node (ref "U1") (pin "40") (pinfunction "PB4_40") (pintype "passive+no_connect"))
    )
    (net (code "68") (name "unconnected-(U1-PC15-Pad4)") (class "Default")
      (node (ref "U1") (pin "4") (pinfunction "PC15_4") (pintype "passive+no_connect"))
    )
  )
)
